# min_system.net
KiCad netlist of a schematic drawn in Altium Designer
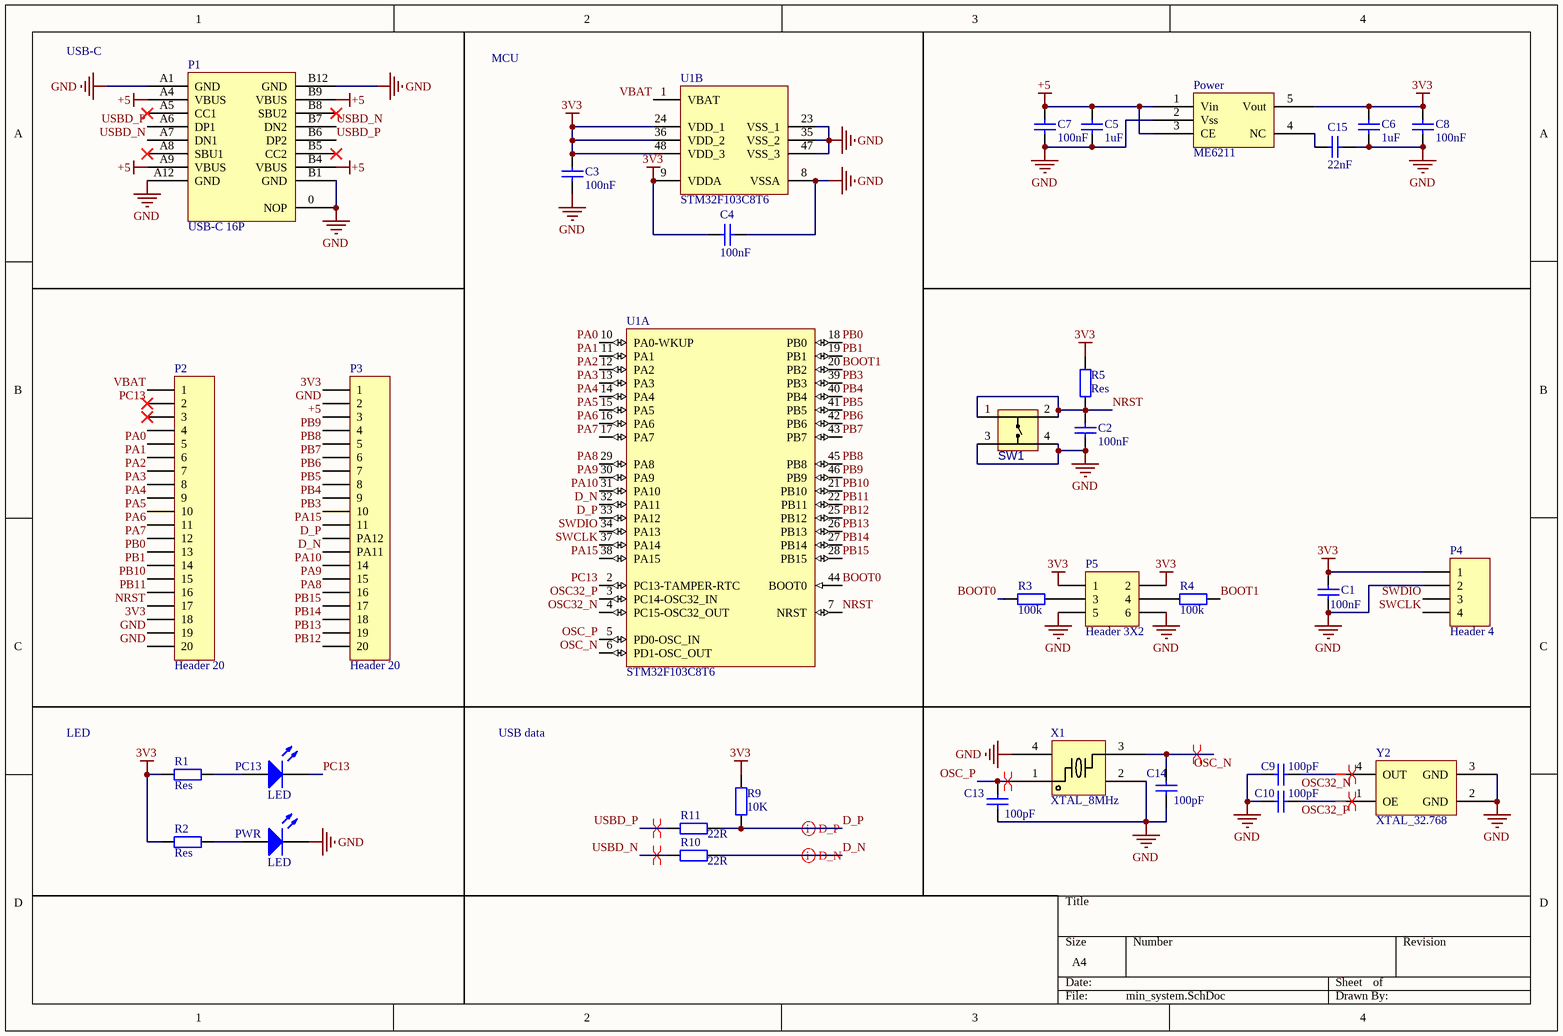
[diagram p0: min_system.SchDoc]

(export (version "E")
  (design (tool "Eeschema 10.0.6"))
  (components
    (comp (ref "C1")
      (value "100nF")
      (footprint "1608[0603]")
      (description "Capacitor")
      (fields (field (name "PUBLISHER") "Altium Limited"))
      (libsource (lib "Miscellaneous Devices") (part "Cap"))
    )
    (comp (ref "C2")
      (value "100nF")
      (footprint "1608[0603]")
      (description "Capacitor")
      (fields (field (name "PUBLISHER") "Altium Limited"))
      (libsource (lib "Miscellaneous Devices") (part "Cap"))
    )
    (comp (ref "C3")
      (value "100nF")
      (footprint "1608[0603]")
      (description "Capacitor")
      (fields (field (name "PUBLISHER") "Altium Limited"))
      (libsource (lib "Miscellaneous Devices") (part "Cap"))
    )
    (comp (ref "C4")
      (value "100nF")
      (footprint "1608[0603]")
      (description "Capacitor")
      (fields (field (name "PUBLISHER") "Altium Limited"))
      (libsource (lib "Miscellaneous Devices") (part "Cap"))
    )
    (comp (ref "C5")
      (value "1uF")
      (footprint "6-0805_M")
      (description "Capacitor")
      (fields (field (name "PUBLISHER") "Altium Limited"))
      (libsource (lib "Miscellaneous Devices") (part "Cap"))
    )
    (comp (ref "C6")
      (value "1uF")
      (footprint "6-0805_M")
      (description "Capacitor")
      (fields (field (name "PUBLISHER") "Altium Limited"))
      (libsource (lib "Miscellaneous Devices") (part "Cap"))
    )
    (comp (ref "C7")
      (value "100nF")
      (footprint "1608[0603]")
      (description "Capacitor")
      (fields (field (name "PUBLISHER") "Altium Limited"))
      (libsource (lib "Miscellaneous Devices") (part "Cap"))
    )
    (comp (ref "C8")
      (value "100nF")
      (footprint "1608[0603]")
      (description "Capacitor")
      (fields (field (name "PUBLISHER") "Altium Limited"))
      (libsource (lib "Miscellaneous Devices") (part "Cap"))
    )
    (comp (ref "C9")
      (value "100pF")
      (footprint "1608[0603]")
      (description "Capacitor")
      (fields (field (name "Comment") "Cap") (field (name "PUBLISHER") "Altium Limited"))
      (libsource (lib "Miscellaneous Devices") (part "Cap"))
    )
    (comp (ref "C10")
      (value "100pF")
      (footprint "1608[0603]")
      (description "Capacitor")
      (fields (field (name "Comment") "Cap") (field (name "PUBLISHER") "Altium Limited"))
      (libsource (lib "Miscellaneous Devices") (part "Cap"))
    )
    (comp (ref "C13")
      (value "100pF")
      (footprint "1608[0603]")
      (description "Capacitor")
      (fields (field (name "Comment") "Cap") (field (name "PUBLISHER") "Altium Limited"))
      (libsource (lib "Miscellaneous Devices") (part "Cap"))
    )
    (comp (ref "C14")
      (value "100pF")
      (footprint "1608[0603]")
      (description "Capacitor")
      (fields (field (name "Comment") "Cap") (field (name "PUBLISHER") "Altium Limited"))
      (libsource (lib "Miscellaneous Devices") (part "Cap"))
    )
    (comp (ref "C15")
      (value "22nF")
      (footprint "1608[0603]")
      (description "Capacitor")
      (fields (field (name "PUBLISHER") "Altium Limited"))
      (libsource (lib "Miscellaneous Devices") (part "Cap"))
    )
    (comp (ref "P1") (value "USB-C 16P") (footprint "USB-C 16P") (libsource (lib "USB") (part "USB-C 16P")))
    (comp (ref "P2")
      (value "Header 20")
      (footprint "HDR1X20")
      (description "Header, 20-Pin")
      (fields (field (name "PUBLISHER") "Altium Limited"))
      (libsource (lib "Miscellaneous Connectors") (part "Header 20"))
    )
    (comp (ref "P3")
      (value "Header 20")
      (footprint "HDR1X20")
      (description "Header, 20-Pin")
      (fields (field (name "PUBLISHER") "Altium Limited"))
      (libsource (lib "Miscellaneous Connectors") (part "Header 20"))
    )
    (comp (ref "P4")
      (value "Header 4")
      (footprint "HDR1X4")
      (description "Header, 4-Pin")
      (fields (field (name "PUBLISHER") "Altium Limited"))
      (libsource (lib "Miscellaneous Connectors") (part "Header 4"))
    )
    (comp (ref "P5")
      (value "Header 3X2")
      (footprint "HDR2X3")
      (description "Header, 3-Pin, Dual row")
      (fields (field (name "PUBLISHER") "Altium Limited"))
      (libsource (lib "Miscellaneous Connectors") (part "Header 3X2"))
    )
    (comp (ref "PC13")
      (value "LED")
      (footprint "LED_0603")
      (description "Typical INFRARED GaAs LED")
      (fields (field (name "PUBLISHER") "Altium Limited"))
      (libsource (lib "Miscellaneous Devices") (part "LED"))
    )
    (comp (ref "Power")
      (value "ME6211")
      (footprint "ME6211")
      (description "SOT23-5")
      (libsource (lib "Common_Modules") (part "ME6211"))
    )
    (comp (ref "PWR")
      (value "LED")
      (footprint "LED_0603")
      (description "Typical INFRARED GaAs LED")
      (fields (field (name "PUBLISHER") "Altium Limited"))
      (libsource (lib "Miscellaneous Devices") (part "LED"))
    )
    (comp (ref "R1")
      (value "Res")
      (footprint "1608[0603]")
      (description "Resistor")
      (fields (field (name "PUBLISHER") "Altium Limited"))
      (libsource (lib "Miscellaneous Devices") (part "Res"))
    )
    (comp (ref "R2")
      (value "Res")
      (footprint "1608[0603]")
      (description "Resistor")
      (fields (field (name "PUBLISHER") "Altium Limited"))
      (libsource (lib "Miscellaneous Devices") (part "Res"))
    )
    (comp (ref "R3")
      (value "100k")
      (footprint "1608[0603]")
      (description "Resistor")
      (fields (field (name "PUBLISHER") "Altium Limited"))
      (libsource (lib "Miscellaneous Devices") (part "Res"))
    )
    (comp (ref "R4")
      (value "100k")
      (footprint "1608[0603]")
      (description "Resistor")
      (fields (field (name "PUBLISHER") "Altium Limited"))
      (libsource (lib "Miscellaneous Devices") (part "Res"))
    )
    (comp (ref "R5")
      (value "Res")
      (footprint "1608[0603]")
      (description "Resistor")
      (fields (field (name "PUBLISHER") "Altium Limited"))
      (libsource (lib "") (part "Res_1"))
    )
    (comp (ref "R9")
      (value "10K")
      (footprint "1608[0603]")
      (description "Resistor")
      (fields (field (name "PUBLISHER") "Altium Limited"))
      (libsource (lib "") (part "Res_2"))
    )
    (comp (ref "R10")
      (value "22R")
      (footprint "1608[0603]")
      (description "Resistor")
      (fields (field (name "PUBLISHER") "Altium Limited"))
      (libsource (lib "Miscellaneous Devices") (part "Res"))
    )
    (comp (ref "R11")
      (value "22R")
      (footprint "1608[0603]")
      (description "Resistor")
      (fields (field (name "PUBLISHER") "Altium Limited"))
      (libsource (lib "Miscellaneous Devices") (part "Res"))
    )
    (comp (ref "SW1")
      (value "TS-1089S-AR02516")
      (footprint "Button-SMD_4P")
      (description "SMD_4P-L4.2-W3.3-P2.15-LS5.1")
      (fields (field (name "MANUFACTURER") "XUNPU(讯普)"))
      (libsource (lib "Miscellaneous Devices") (part "Button-SMD_4P"))
    )
    (comp (ref "U1")
      (value "STM32F103C8T6")
      (footprint "STM-LQFP48_N")
      (libsource (lib "STMicroelectronics STM32 F1") (part "STM32F103C8T6"))
    )
    (comp (ref "X1")
      (value "XTAL_8MHz")
      (footprint "Miscellaneous Devices:XTAL_3225")
      (libsource (lib "Miscellaneous Devices") (part "XTAL_3225"))
    )
    (comp (ref "Y2")
      (value "XTAL_32.768")
      (footprint "MC-306")
      (description "32.768kHz")
      (fields (field (name "PUBLISHER") "Altium Limited"))
      (libsource (lib "Miscellaneous Devices") (part "XTAL_32.768"))
    )
  )
  (nets
    (net (code "1") (name "+5") (class "Default")
      (node (ref "C5") (pin "2") (pinfunction "2_2") (pintype "passive"))
      (node (ref "C7") (pin "2") (pinfunction "2_2") (pintype "passive"))
      (node (ref "P1") (pin "A4") (pinfunction "VBUS_A4") (pintype "passive"))
      (node (ref "P1") (pin "A9") (pinfunction "VBUS_A9") (pintype "passive"))
      (node (ref "P1") (pin "B4") (pinfunction "VBUS_B4") (pintype "passive"))
      (node (ref "P1") (pin "B9") (pinfunction "VBUS_B9") (pintype "passive"))
      (node (ref "P3") (pin "3") (pinfunction "3_3") (pintype "passive"))
      (node (ref "Power") (pin "1") (pinfunction "Vin_1") (pintype "passive"))
      (node (ref "Power") (pin "3") (pinfunction "CE_3") (pintype "passive"))
    )
    (net (code "2") (name "/BOOT0") (class "Default")
      (node (ref "R3") (pin "1") (pinfunction "1_1") (pintype "passive"))
      (node (ref "U1") (pin "44") (pinfunction "BOOT0_44") (pintype "input"))
    )
    (net (code "3") (name "/BOOT1") (class "Default")
      (node (ref "R4") (pin "2") (pinfunction "2_2") (pintype "passive"))
      (node (ref "U1") (pin "20") (pinfunction "PB2_20") (pintype "bidirectional"))
    )
    (net (code "4") (name "/D_N") (class "Default")
      (node (ref "P3") (pin "13") (pinfunction "13_13") (pintype "passive"))
      (node (ref "R10") (pin "2") (pinfunction "2_2") (pintype "passive"))
      (node (ref "U1") (pin "32") (pinfunction "PA11_32") (pintype "bidirectional"))
    )
    (net (code "5") (name "/D_P") (class "Default")
      (node (ref "P3") (pin "12") (pinfunction "12_12") (pintype "passive"))
      (node (ref "R11") (pin "2") (pinfunction "2_2") (pintype "passive"))
      (node (ref "R9") (pin "2") (pinfunction "2_2") (pintype "passive"))
      (node (ref "U1") (pin "33") (pinfunction "PA12_33") (pintype "bidirectional"))
    )
    (net (code "6") (name "/NRST") (class "Default")
      (node (ref "C2") (pin "2") (pinfunction "2_2") (pintype "passive"))
      (node (ref "P2") (pin "17") (pinfunction "17_17") (pintype "passive"))
      (node (ref "R5") (pin "1") (pinfunction "1_1") (pintype "passive"))
      (node (ref "SW1") (pin "1") (pinfunction "1_1") (pintype "passive"))
      (node (ref "SW1") (pin "2") (pinfunction "2_2") (pintype "passive"))
      (node (ref "U1") (pin "7") (pinfunction "NRST_7") (pintype "bidirectional"))
    )
    (net (code "7") (name "/OSC32_N") (class "Default")
      (node (ref "C9") (pin "1") (pinfunction "1_1") (pintype "passive"))
      (node (ref "U1") (pin "4") (pinfunction "PC15-OSC32_OUT_4") (pintype "bidirectional"))
      (node (ref "Y2") (pin "4") (pinfunction "OUT_4") (pintype "passive"))
    )
    (net (code "8") (name "/OSC32_P") (class "Default")
      (node (ref "C10") (pin "2") (pinfunction "2_2") (pintype "passive"))
      (node (ref "U1") (pin "3") (pinfunction "PC14-OSC32_IN_3") (pintype "bidirectional"))
      (node (ref "Y2") (pin "1") (pinfunction "OE_1") (pintype "passive"))
    )
    (net (code "9") (name "/OSC_N") (class "Default")
      (node (ref "C14") (pin "2") (pinfunction "2_2") (pintype "passive"))
      (node (ref "U1") (pin "6") (pinfunction "PD1-OSC_OUT_6") (pintype "bidirectional"))
      (node (ref "X1") (pin "3") (pinfunction "3_3") (pintype "passive"))
    )
    (net (code "10") (name "/OSC_P") (class "Default")
      (node (ref "C13") (pin "1") (pinfunction "1_1") (pintype "passive"))
      (node (ref "U1") (pin "5") (pinfunction "PD0-OSC_IN_5") (pintype "bidirectional"))
      (node (ref "X1") (pin "1") (pinfunction "1_1") (pintype "passive"))
    )
    (net (code "11") (name "/PA0") (class "Default")
      (node (ref "P2") (pin "5") (pinfunction "5_5") (pintype "passive"))
      (node (ref "U1") (pin "10") (pinfunction "PA0-WKUP_10") (pintype "bidirectional"))
    )
    (net (code "12") (name "/PA1") (class "Default")
      (node (ref "P2") (pin "6") (pinfunction "6_6") (pintype "passive"))
      (node (ref "U1") (pin "11") (pinfunction "PA1_11") (pintype "bidirectional"))
    )
    (net (code "13") (name "/PA2") (class "Default")
      (node (ref "P2") (pin "7") (pinfunction "7_7") (pintype "passive"))
      (node (ref "U1") (pin "12") (pinfunction "PA2_12") (pintype "bidirectional"))
    )
    (net (code "14") (name "/PA3") (class "Default")
      (node (ref "P2") (pin "8") (pinfunction "8_8") (pintype "passive"))
      (node (ref "U1") (pin "13") (pinfunction "PA3_13") (pintype "bidirectional"))
    )
    (net (code "15") (name "/PA4") (class "Default")
      (node (ref "P2") (pin "9") (pinfunction "9_9") (pintype "passive"))
      (node (ref "U1") (pin "14") (pinfunction "PA4_14") (pintype "bidirectional"))
    )
    (net (code "16") (name "/PA5") (class "Default")
      (node (ref "P2") (pin "10") (pinfunction "10_10") (pintype "passive"))
      (node (ref "U1") (pin "15") (pinfunction "PA5_15") (pintype "bidirectional"))
    )
    (net (code "17") (name "/PA6") (class "Default")
      (node (ref "P2") (pin "11") (pinfunction "11_11") (pintype "passive"))
      (node (ref "U1") (pin "16") (pinfunction "PA6_16") (pintype "bidirectional"))
    )
    (net (code "18") (name "/PA7") (class "Default")
      (node (ref "P2") (pin "12") (pinfunction "12_12") (pintype "passive"))
      (node (ref "U1") (pin "17") (pinfunction "PA7_17") (pintype "bidirectional"))
    )
    (net (code "19") (name "/PA8") (class "Default")
      (node (ref "P3") (pin "16") (pinfunction "16_16") (pintype "passive"))
      (node (ref "U1") (pin "29") (pinfunction "PA8_29") (pintype "bidirectional"))
    )
    (net (code "20") (name "/PA9") (class "Default")
      (node (ref "P3") (pin "15") (pinfunction "15_15") (pintype "passive"))
      (node (ref "U1") (pin "30") (pinfunction "PA9_30") (pintype "bidirectional"))
    )
    (net (code "21") (name "/PA10") (class "Default")
      (node (ref "P3") (pin "14") (pinfunction "14_14") (pintype "passive"))
      (node (ref "U1") (pin "31") (pinfunction "PA10_31") (pintype "bidirectional"))
    )
    (net (code "22") (name "/PA15") (class "Default")
      (node (ref "P3") (pin "11") (pinfunction "11_11") (pintype "passive"))
      (node (ref "U1") (pin "38") (pinfunction "PA15_38") (pintype "bidirectional"))
    )
    (net (code "23") (name "/PB0") (class "Default")
      (node (ref "P2") (pin "13") (pinfunction "13_13") (pintype "passive"))
      (node (ref "U1") (pin "18") (pinfunction "PB0_18") (pintype "bidirectional"))
    )
    (net (code "24") (name "/PB1") (class "Default")
      (node (ref "P2") (pin "14") (pinfunction "14_14") (pintype "passive"))
      (node (ref "U1") (pin "19") (pinfunction "PB1_19") (pintype "bidirectional"))
    )
    (net (code "25") (name "/PB3") (class "Default")
      (node (ref "P3") (pin "10") (pinfunction "10_10") (pintype "passive"))
      (node (ref "U1") (pin "39") (pinfunction "PB3_39") (pintype "bidirectional"))
    )
    (net (code "26") (name "/PB4") (class "Default")
      (node (ref "P3") (pin "9") (pinfunction "9_9") (pintype "passive"))
      (node (ref "U1") (pin "40") (pinfunction "PB4_40") (pintype "bidirectional"))
    )
    (net (code "27") (name "/PB5") (class "Default")
      (node (ref "P3") (pin "8") (pinfunction "8_8") (pintype "passive"))
      (node (ref "U1") (pin "41") (pinfunction "PB5_41") (pintype "bidirectional"))
    )
    (net (code "28") (name "/PB6") (class "Default")
      (node (ref "P3") (pin "7") (pinfunction "7_7") (pintype "passive"))
      (node (ref "U1") (pin "42") (pinfunction "PB6_42") (pintype "bidirectional"))
    )
    (net (code "29") (name "/PB7") (class "Default")
      (node (ref "P3") (pin "6") (pinfunction "6_6") (pintype "passive"))
      (node (ref "U1") (pin "43") (pinfunction "PB7_43") (pintype "bidirectional"))
    )
    (net (code "30") (name "/PB8") (class "Default")
      (node (ref "P3") (pin "5") (pinfunction "5_5") (pintype "passive"))
      (node (ref "U1") (pin "45") (pinfunction "PB8_45") (pintype "bidirectional"))
    )
    (net (code "31") (name "/PB9") (class "Default")
      (node (ref "P3") (pin "4") (pinfunction "4_4") (pintype "passive"))
      (node (ref "U1") (pin "46") (pinfunction "PB9_46") (pintype "bidirectional"))
    )
    (net (code "32") (name "/PB10") (class "Default")
      (node (ref "P2") (pin "15") (pinfunction "15_15") (pintype "passive"))
      (node (ref "U1") (pin "21") (pinfunction "PB10_21") (pintype "bidirectional"))
    )
    (net (code "33") (name "/PB11") (class "Default")
      (node (ref "P2") (pin "16") (pinfunction "16_16") (pintype "passive"))
      (node (ref "U1") (pin "22") (pinfunction "PB11_22") (pintype "bidirectional"))
    )
    (net (code "34") (name "/PB12") (class "Default")
      (node (ref "P3") (pin "20") (pinfunction "20_20") (pintype "passive"))
      (node (ref "U1") (pin "25") (pinfunction "PB12_25") (pintype "bidirectional"))
    )
    (net (code "35") (name "/PB13") (class "Default")
      (node (ref "P3") (pin "19") (pinfunction "19_19") (pintype "passive"))
      (node (ref "U1") (pin "26") (pinfunction "PB13_26") (pintype "bidirectional"))
    )
    (net (code "36") (name "/PB14") (class "Default")
      (node (ref "P3") (pin "18") (pinfunction "18_18") (pintype "passive"))
      (node (ref "U1") (pin "27") (pinfunction "PB14_27") (pintype "bidirectional"))
    )
    (net (code "37") (name "/PB15") (class "Default")
      (node (ref "P3") (pin "17") (pinfunction "17_17") (pintype "passive"))
      (node (ref "U1") (pin "28") (pinfunction "PB15_28") (pintype "bidirectional"))
    )
    (net (code "38") (name "/PC13") (class "Default")
      (node (ref "P2") (pin "2") (pinfunction "2_2") (pintype "passive"))
      (node (ref "PC13") (pin "2") (pinfunction "K_2") (pintype "passive"))
      (node (ref "U1") (pin "2") (pinfunction "PC13-TAMPER-RTC_2") (pintype "bidirectional"))
    )
    (net (code "39") (name "/SWCLK") (class "Default")
      (node (ref "P4") (pin "4") (pinfunction "4_4") (pintype "passive"))
      (node (ref "U1") (pin "37") (pinfunction "PA14_37") (pintype "bidirectional"))
    )
    (net (code "40") (name "/SWDIO") (class "Default")
      (node (ref "P4") (pin "3") (pinfunction "3_3") (pintype "passive"))
      (node (ref "U1") (pin "34") (pinfunction "PA13_34") (pintype "bidirectional"))
    )
    (net (code "41") (name "/USBD_N") (class "Default")
      (node (ref "P1") (pin "A7") (pinfunction "DN1_A7") (pintype "passive"))
      (node (ref "P1") (pin "B7") (pinfunction "DN2_B7") (pintype "passive"))
      (node (ref "R10") (pin "1") (pinfunction "1_1") (pintype "passive"))
    )
    (net (code "42") (name "/USBD_P") (class "Default")
      (node (ref "P1") (pin "A6") (pinfunction "DP1_A6") (pintype "passive"))
      (node (ref "P1") (pin "B6") (pinfunction "DP2_B6") (pintype "passive"))
      (node (ref "R11") (pin "1") (pinfunction "1_1") (pintype "passive"))
    )
    (net (code "43") (name "/VBAT") (class "Default")
      (node (ref "P2") (pin "1") (pinfunction "1_1") (pintype "passive"))
      (node (ref "U1") (pin "1") (pinfunction "VBAT_1") (pintype "power_in"))
    )
    (net (code "44") (name "3V3") (class "Default")
      (node (ref "C1") (pin "2") (pinfunction "2_2") (pintype "passive"))
      (node (ref "C3") (pin "2") (pinfunction "2_2") (pintype "passive"))
      (node (ref "C4") (pin "2") (pinfunction "2_2") (pintype "passive"))
      (node (ref "C6") (pin "2") (pinfunction "2_2") (pintype "passive"))
      (node (ref "C8") (pin "2") (pinfunction "2_2") (pintype "passive"))
      (node (ref "P2") (pin "18") (pinfunction "18_18") (pintype "passive"))
      (node (ref "P3") (pin "1") (pinfunction "1_1") (pintype "passive"))
      (node (ref "P4") (pin "1") (pinfunction "1_1") (pintype "passive"))
      (node (ref "P5") (pin "1") (pinfunction "1_1") (pintype "passive"))
      (node (ref "P5") (pin "2") (pinfunction "2_2") (pintype "passive"))
      (node (ref "Power") (pin "5") (pinfunction "Vout_5") (pintype "passive"))
      (node (ref "R1") (pin "1") (pinfunction "1_1") (pintype "passive"))
      (node (ref "R2") (pin "1") (pinfunction "1_1") (pintype "passive"))
      (node (ref "R5") (pin "2") (pinfunction "2_2") (pintype "passive"))
      (node (ref "R9") (pin "1") (pinfunction "1_1") (pintype "passive"))
      (node (ref "U1") (pin "24") (pinfunction "VDD_1_24") (pintype "power_in"))
      (node (ref "U1") (pin "36") (pinfunction "VDD_2_36") (pintype "power_in"))
      (node (ref "U1") (pin "48") (pinfunction "VDD_3_48") (pintype "power_in"))
      (node (ref "U1") (pin "9") (pinfunction "VDDA_9") (pintype "power_in"))
    )
    (net (code "45") (name "GND") (class "Default")
      (node (ref "C1") (pin "1") (pinfunction "1_1") (pintype "passive"))
      (node (ref "C10") (pin "1") (pinfunction "1_1") (pintype "passive"))
      (node (ref "C13") (pin "2") (pinfunction "2_2") (pintype "passive"))
      (node (ref "C14") (pin "1") (pinfunction "1_1") (pintype "passive"))
      (node (ref "C15") (pin "2") (pinfunction "2_2") (pintype "passive"))
      (node (ref "C2") (pin "1") (pinfunction "1_1") (pintype "passive"))
      (node (ref "C3") (pin "1") (pinfunction "1_1") (pintype "passive"))
      (node (ref "C4") (pin "1") (pinfunction "1_1") (pintype "passive"))
      (node (ref "C5") (pin "1") (pinfunction "1_1") (pintype "passive"))
      (node (ref "C6") (pin "1") (pinfunction "1_1") (pintype "passive"))
      (node (ref "C7") (pin "1") (pinfunction "1_1") (pintype "passive"))
      (node (ref "C8") (pin "1") (pinfunction "1_1") (pintype "passive"))
      (node (ref "C9") (pin "2") (pinfunction "2_2") (pintype "passive"))
      (node (ref "P1") (pin "0") (pinfunction "NOP_0") (pintype "passive"))
      (node (ref "P1") (pin "A1") (pinfunction "GND_A1") (pintype "passive"))
      (node (ref "P1") (pin "A12") (pinfunction "GND_A12") (pintype "passive"))
      (node (ref "P1") (pin "B1") (pinfunction "GND_B1") (pintype "passive"))
      (node (ref "P1") (pin "B12") (pinfunction "GND_B12") (pintype "passive"))
      (node (ref "P2") (pin "19") (pinfunction "19_19") (pintype "passive"))
      (node (ref "P2") (pin "20") (pinfunction "20_20") (pintype "passive"))
      (node (ref "P3") (pin "2") (pinfunction "2_2") (pintype "passive"))
      (node (ref "P4") (pin "2") (pinfunction "2_2") (pintype "passive"))
      (node (ref "P5") (pin "5") (pinfunction "5_5") (pintype "passive"))
      (node (ref "P5") (pin "6") (pinfunction "6_6") (pintype "passive"))
      (node (ref "PWR") (pin "2") (pinfunction "K_2") (pintype "passive"))
      (node (ref "Power") (pin "2") (pinfunction "Vss_2") (pintype "passive"))
      (node (ref "SW1") (pin "3") (pinfunction "3_3") (pintype "passive"))
      (node (ref "SW1") (pin "4") (pinfunction "4_4") (pintype "passive"))
      (node (ref "U1") (pin "23") (pinfunction "VSS_1_23") (pintype "power_in"))
      (node (ref "U1") (pin "35") (pinfunction "VSS_2_35") (pintype "power_in"))
      (node (ref "U1") (pin "47") (pinfunction "VSS_3_47") (pintype "power_in"))
      (node (ref "U1") (pin "8") (pinfunction "VSSA_8") (pintype "power_in"))
      (node (ref "X1") (pin "2") (pinfunction "2_2") (pintype "passive"))
      (node (ref "X1") (pin "4") (pinfunction "4_4") (pintype "passive"))
      (node (ref "Y2") (pin "2") (pinfunction "GND_2") (pintype "passive"))
      (node (ref "Y2") (pin "3") (pinfunction "GND_3") (pintype "passive"))
    )
    (net (code "46") (name "Net-(P5-Pad3)") (class "Default")
      (node (ref "P5") (pin "3") (pinfunction "3_3") (pintype "passive"))
      (node (ref "R3") (pin "2") (pinfunction "2_2") (pintype "passive"))
    )
    (net (code "47") (name "Net-(P5-Pad4)") (class "Default")
      (node (ref "P5") (pin "4") (pinfunction "4_4") (pintype "passive"))
      (node (ref "R4") (pin "1") (pinfunction "1_1") (pintype "passive"))
    )
    (net (code "48") (name "Net-(PC13-A)") (class "Default")
      (node (ref "PC13") (pin "1") (pinfunction "A_1") (pintype "passive"))
      (node (ref "R1") (pin "2") (pinfunction "2_2") (pintype "passive"))
    )
    (net (code "49") (name "Net-(PWR-A)") (class "Default")
      (node (ref "PWR") (pin "1") (pinfunction "A_1") (pintype "passive"))
      (node (ref "R2") (pin "2") (pinfunction "2_2") (pintype "passive"))
    )
    (net (code "50") (name "Net-(Power-NC)") (class "Default")
      (node (ref "C15") (pin "1") (pinfunction "1_1") (pintype "passive"))
      (node (ref "Power") (pin "4") (pinfunction "NC_4") (pintype "passive"))
    )
    (net (code "51") (name "unconnected-(P1-CC1-PadA5)") (class "Default")
      (node (ref "P1") (pin "A5") (pinfunction "CC1_A5") (pintype "passive+no_connect"))
    )
    (net (code "52") (name "unconnected-(P1-CC2-PadB5)") (class "Default")
      (node (ref "P1") (pin "B5") (pinfunction "CC2_B5") (pintype "passive+no_connect"))
    )
    (net (code "53") (name "unconnected-(P1-SBU1-PadA8)") (class "Default")
      (node (ref "P1") (pin "A8") (pinfunction "SBU1_A8") (pintype "passive+no_connect"))
    )
    (net (code "54") (name "unconnected-(P1-SBU2-PadB8)") (class "Default")
      (node (ref "P1") (pin "B8") (pinfunction "SBU2_B8") (pintype "passive+no_connect"))
    )
    (net (code "55") (name "unconnected-(P2-Pad3)") (class "Default")
      (node (ref "P2") (pin "3") (pinfunction "3_3") (pintype "passive+no_connect"))
    )
    (net (code "56") (name "unconnected-(P2-Pad4)") (class "Default")
      (node (ref "P2") (pin "4") (pinfunction "4_4") (pintype "passive"))
    )
  )
)
